# LCDTFTAVDD_AP3031.net
KiCad netlist of a schematic drawn in Altium Designer
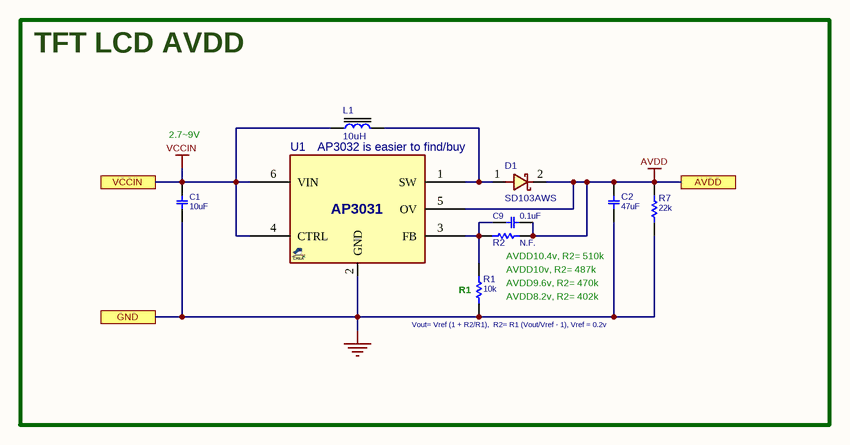
[diagram p0: LCDTFTAVDD_AP3031.SchDoc]

(export (version "E")
  (design (tool "Eeschema 10.0.6"))
  (components
    (comp (ref "C1")
      (value "10uF")
      (footprint "C0402")
      (description "CAP, MLCC")
      (fields (field (name "MANF_P#") "CL10A106MO8NQNC") (field (name "MANF") "Samsung"))
      (libsource (lib "passive_smd") (part "CAP_SMD_MLCC"))
    )
    (comp (ref "C2")
      (value "47uF")
      (footprint "C1206")
      (description "CAP, MLCC")
      (fields (field (name "MANF_P#") "GRM31CR61E476ME44L") (field (name "MANF") "Murata"))
      (libsource (lib "passive_smd") (part "CAP_SMD_MLCC"))
    )
    (comp (ref "C9")
      (value "0.1uF")
      (footprint "C0402")
      (description "CAP, MLCC, 100nF, 50V, X7R, 10%, 0402C")
      (fields (field (name "MANF") "Murata") (field (name "MANF_P#") "GCM155R71H104KE02D"))
      (libsource (lib "passive_mlcc_smd") (part "CAP_SMD_MLCC_100n50V"))
    )
    (comp (ref "D1")
      (value "SD103AWS")
      (footprint "D_SOD323")
      (description "DIODE, SCHOTTKY, 40V, 2A")
      (fields (field (name "MANF") "DIODES"))
      (libsource (lib "diode") (part "DIODE_SMD_SCHOTTKY_1N5819"))
    )
    (comp (ref "L1")
      (value "10uH")
      (footprint "L_4")
      (description "INDUCTOR, POWER, SMD")
      (fields (field (name "MANF_P#") "GCD43-100MC"))
      (libsource (lib "passive") (part "INDPWR_SMD"))
    )
    (comp (ref "R1")
      (value "10k")
      (footprint "R0402")
      (description "RESISTOR, SMD, 20K, 0402")
      (fields (field (name "MANF") "Yageo") (field (name "MANF_P#") "RK73H1ETTP2002F"))
      (libsource (lib "chila_passive") (part "RES_SMD"))
    )
    (comp (ref "R2")
      (value "N.F.")
      (footprint "R0402")
      (description "RESISTOR, SMD, 20K, 0402")
      (fields (field (name "MANF") "Yageo") (field (name "MANF_P#") "RK73H1ETTP2002F"))
      (libsource (lib "chila_passive") (part "RES_SMD"))
    )
    (comp (ref "R7")
      (value "22k")
      (footprint "R0402")
      (description "RESISTOR, SMD, 20K, 0402")
      (fields (field (name "MANF") "Yageo") (field (name "MANF_P#") "RK73H1ETTP2002F"))
      (libsource (lib "chila_passive") (part "RES_SMD"))
    )
    (comp (ref "U1")
      (value "AP3031")
      (footprint "SOT23_6")
      (description "REG, Switching, Boost, 1.4A, ADJ, 1MHz, SOT-23-6")
      (fields (field (name "MANF_P#") "AP3031K") (field (name "MANF") "Diodes"))
      (libsource (lib "pwr_switching_boost") (part "VREG_AP3031_SOT23"))
    )
  )
  (nets
    (net (code "1") (name "AVDD") (class "Default")
      (node (ref "C2") (pin "2") (pinfunction "2_2") (pintype "passive"))
      (node (ref "C9") (pin "1") (pinfunction "1_1") (pintype "passive"))
      (node (ref "D1") (pin "2") (pinfunction "2_2") (pintype "passive"))
      (node (ref "R2") (pin "2") (pinfunction "2_2") (pintype "passive"))
      (node (ref "R7") (pin "1") (pinfunction "1_1") (pintype "passive"))
      (node (ref "U1") (pin "5") (pinfunction "OV_5") (pintype "passive"))
    )
    (net (code "2") (name "GND") (class "Default")
      (node (ref "C1") (pin "1") (pinfunction "1_1") (pintype "passive"))
      (node (ref "C2") (pin "1") (pinfunction "1_1") (pintype "passive"))
      (node (ref "R1") (pin "2") (pinfunction "2_2") (pintype "passive"))
      (node (ref "R7") (pin "2") (pinfunction "2_2") (pintype "passive"))
      (node (ref "U1") (pin "2") (pinfunction "GND_2") (pintype "tri_state"))
    )
    (net (code "3") (name "Net-(U1-FB)") (class "Default")
      (node (ref "C9") (pin "2") (pinfunction "2_2") (pintype "passive"))
      (node (ref "R1") (pin "1") (pinfunction "1_1") (pintype "passive"))
      (node (ref "R2") (pin "1") (pinfunction "1_1") (pintype "passive"))
      (node (ref "U1") (pin "3") (pinfunction "FB_3") (pintype "passive"))
    )
    (net (code "4") (name "Net-(U1-SW)") (class "Default")
      (node (ref "D1") (pin "1") (pinfunction "1_1") (pintype "passive"))
      (node (ref "L1") (pin "2") (pinfunction "2_2") (pintype "passive"))
      (node (ref "U1") (pin "1") (pinfunction "SW_1") (pintype "passive"))
    )
    (net (code "5") (name "VCCIN") (class "Default")
      (node (ref "C1") (pin "2") (pinfunction "2_2") (pintype "passive"))
      (node (ref "L1") (pin "1") (pinfunction "1_1") (pintype "passive"))
      (node (ref "U1") (pin "4") (pinfunction "CTRL_4") (pintype "passive"))
      (node (ref "U1") (pin "6") (pinfunction "VIN_6") (pintype "passive"))
    )
  )
)
